# Analog_-_High_Speed_DE.net
KiCad netlist of a schematic drawn in Altium Designer
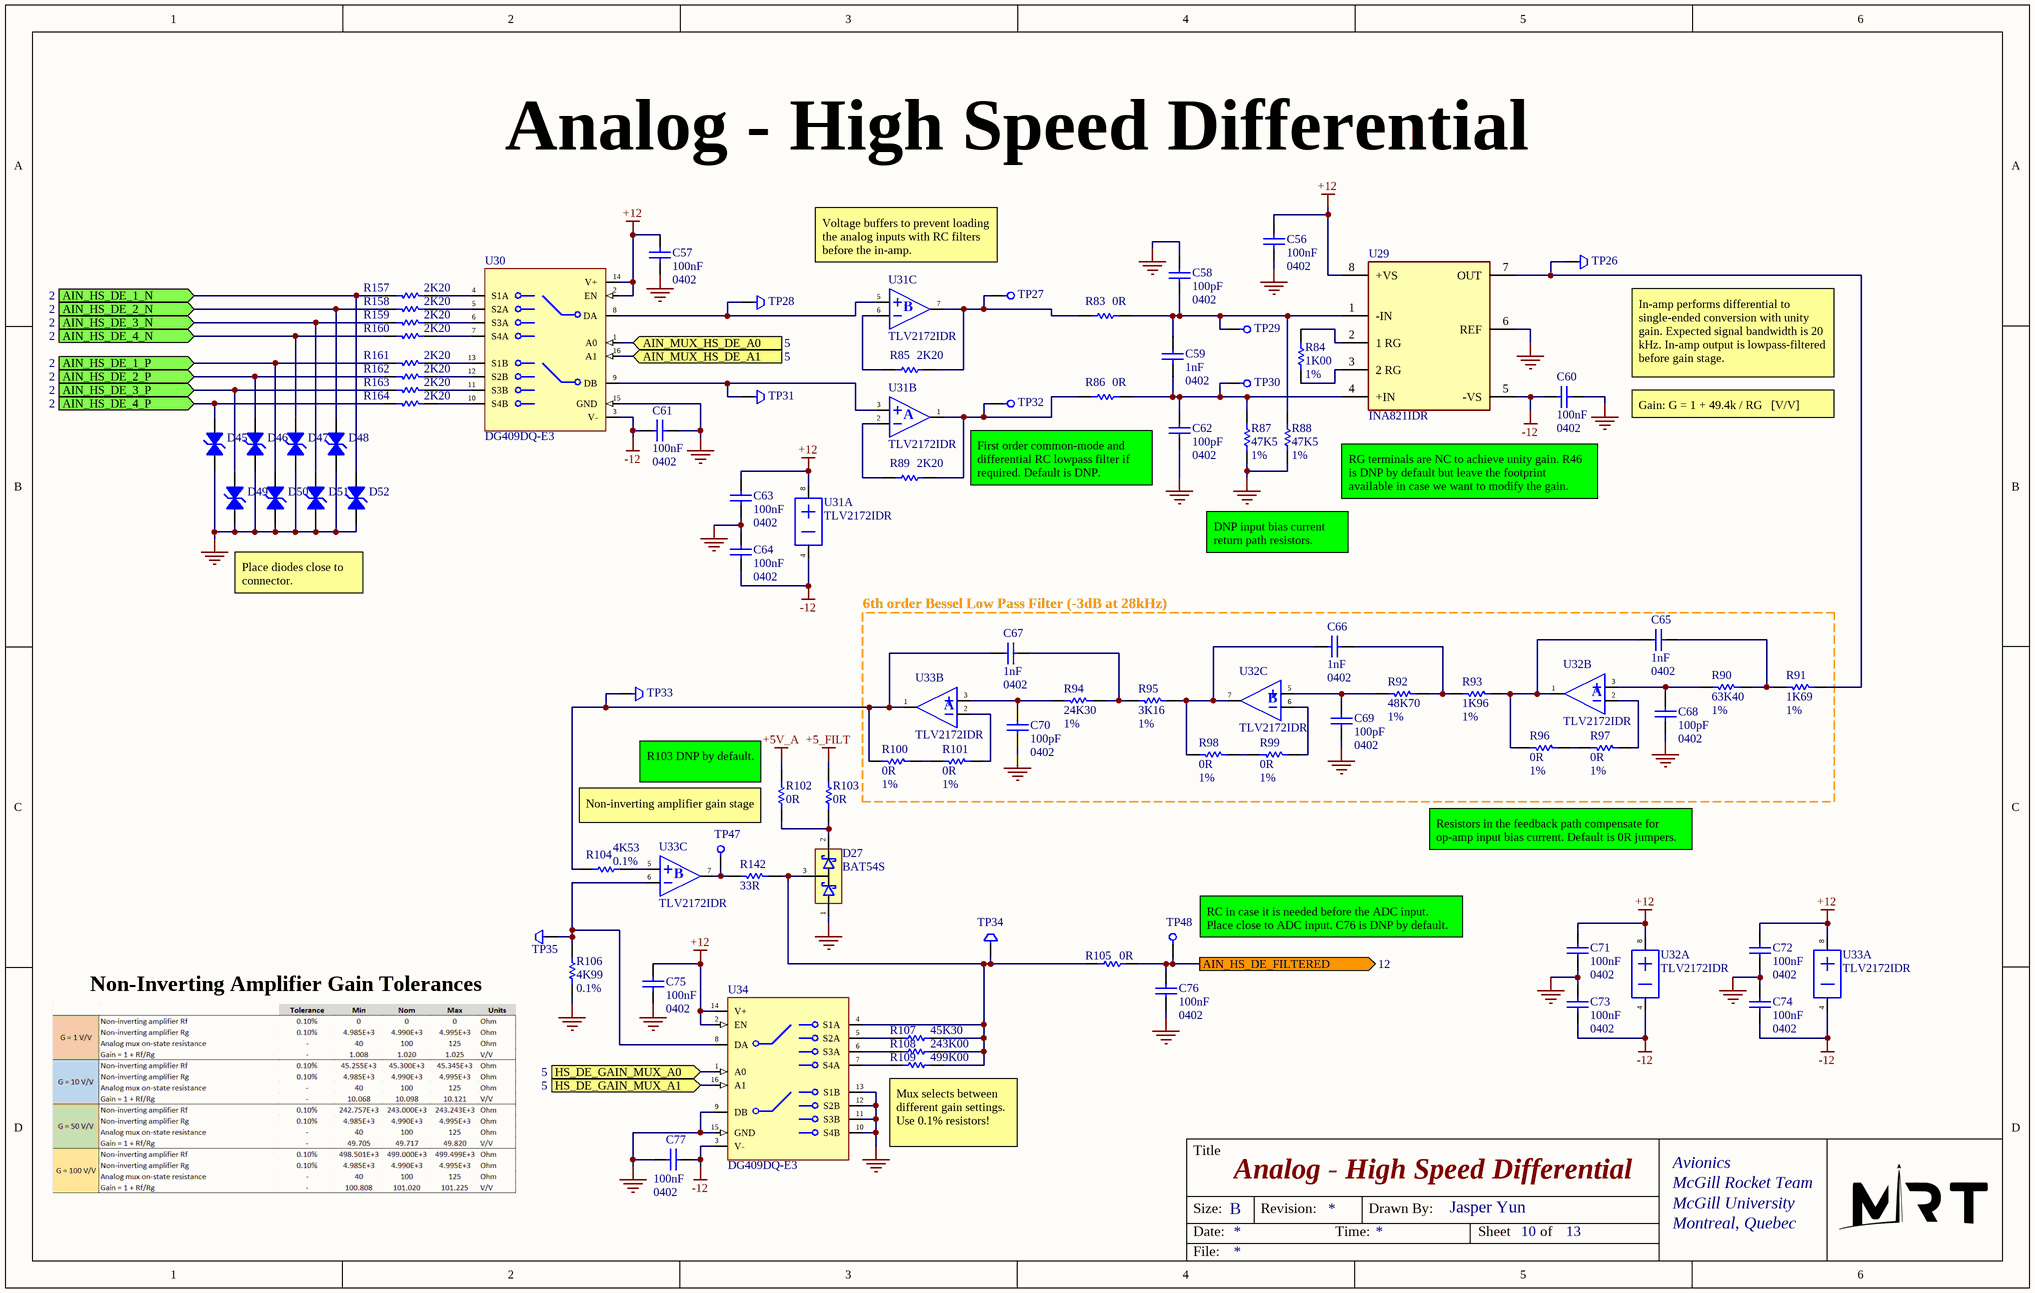
[diagram p0: Analog - High Speed DE.SchDoc]

(export (version "E")
  (design (tool "Eeschema 10.0.6"))
  (components
    (comp (ref "C56")
      (value "100nF")
      (footprint "0402 CAP")
      (description "Capacitor")
      (fields (field (name "ALTIUM_VALUE") "0402") (field (name "PUBLISHER") "Altium Limited"))
      (libsource (lib "Miscellaneous Devices") (part "Cap"))
    )
    (comp (ref "C57")
      (value "100nF")
      (footprint "0402 CAP")
      (description "Capacitor")
      (fields (field (name "ALTIUM_VALUE") "0402") (field (name "PUBLISHER") "Altium Limited"))
      (libsource (lib "Miscellaneous Devices") (part "Cap"))
    )
    (comp (ref "C58")
      (value "100pF")
      (footprint "0402 CAP")
      (description "Capacitor")
      (fields (field (name "ALTIUM_VALUE") "0402") (field (name "PUBLISHER") "Altium Limited"))
      (libsource (lib "Miscellaneous Devices") (part "Cap"))
    )
    (comp (ref "C59")
      (value "1nF")
      (footprint "0402 CAP")
      (description "Capacitor")
      (fields (field (name "ALTIUM_VALUE") "0402") (field (name "PUBLISHER") "Altium Limited"))
      (libsource (lib "Miscellaneous Devices") (part "Cap"))
    )
    (comp (ref "C60")
      (value "100nF")
      (footprint "0402 CAP")
      (description "Capacitor")
      (fields (field (name "ALTIUM_VALUE") "0402") (field (name "PUBLISHER") "Altium Limited"))
      (libsource (lib "Miscellaneous Devices") (part "Cap"))
    )
    (comp (ref "C61")
      (value "100nF")
      (footprint "0402 CAP")
      (description "Capacitor")
      (fields (field (name "ALTIUM_VALUE") "0402") (field (name "PUBLISHER") "Altium Limited"))
      (libsource (lib "Miscellaneous Devices") (part "Cap"))
    )
    (comp (ref "C62")
      (value "100pF")
      (footprint "0402 CAP")
      (description "Capacitor")
      (fields (field (name "ALTIUM_VALUE") "0402") (field (name "PUBLISHER") "Altium Limited"))
      (libsource (lib "Miscellaneous Devices") (part "Cap"))
    )
    (comp (ref "C63")
      (value "100nF")
      (footprint "0402 CAP")
      (description "Capacitor")
      (fields (field (name "ALTIUM_VALUE") "0402") (field (name "PUBLISHER") "Altium Limited"))
      (libsource (lib "Miscellaneous Devices") (part "Cap"))
    )
    (comp (ref "C64")
      (value "100nF")
      (footprint "0402 CAP")
      (description "Capacitor")
      (fields (field (name "ALTIUM_VALUE") "0402") (field (name "PUBLISHER") "Altium Limited"))
      (libsource (lib "Miscellaneous Devices") (part "Cap"))
    )
    (comp (ref "C65")
      (value "1nF")
      (footprint "0402 CAP")
      (description "Capacitor")
      (fields (field (name "ALTIUM_VALUE") "0402") (field (name "PUBLISHER") "Altium Limited"))
      (libsource (lib "Miscellaneous Devices") (part "Cap"))
    )
    (comp (ref "C66")
      (value "1nF")
      (footprint "0402 CAP")
      (description "Capacitor")
      (fields (field (name "ALTIUM_VALUE") "0402") (field (name "PUBLISHER") "Altium Limited"))
      (libsource (lib "Miscellaneous Devices") (part "Cap"))
    )
    (comp (ref "C67")
      (value "1nF")
      (footprint "0402 CAP")
      (description "Capacitor")
      (fields (field (name "ALTIUM_VALUE") "0402") (field (name "PUBLISHER") "Altium Limited"))
      (libsource (lib "Miscellaneous Devices") (part "Cap"))
    )
    (comp (ref "C68")
      (value "100pF")
      (footprint "0402 CAP")
      (description "Capacitor")
      (fields (field (name "ALTIUM_VALUE") "0402") (field (name "PUBLISHER") "Altium Limited"))
      (libsource (lib "Miscellaneous Devices") (part "Cap"))
    )
    (comp (ref "C69")
      (value "100pF")
      (footprint "0402 CAP")
      (description "Capacitor")
      (fields (field (name "ALTIUM_VALUE") "0402") (field (name "PUBLISHER") "Altium Limited"))
      (libsource (lib "Miscellaneous Devices") (part "Cap"))
    )
    (comp (ref "C70")
      (value "100pF")
      (footprint "0402 CAP")
      (description "Capacitor")
      (fields (field (name "ALTIUM_VALUE") "0402") (field (name "PUBLISHER") "Altium Limited"))
      (libsource (lib "Miscellaneous Devices") (part "Cap"))
    )
    (comp (ref "C71")
      (value "100nF")
      (footprint "0402 CAP")
      (description "Capacitor")
      (fields (field (name "ALTIUM_VALUE") "0402") (field (name "PUBLISHER") "Altium Limited"))
      (libsource (lib "Miscellaneous Devices") (part "Cap"))
    )
    (comp (ref "C72")
      (value "100nF")
      (footprint "0402 CAP")
      (description "Capacitor")
      (fields (field (name "ALTIUM_VALUE") "0402") (field (name "PUBLISHER") "Altium Limited"))
      (libsource (lib "Miscellaneous Devices") (part "Cap"))
    )
    (comp (ref "C73")
      (value "100nF")
      (footprint "0402 CAP")
      (description "Capacitor")
      (fields (field (name "ALTIUM_VALUE") "0402") (field (name "PUBLISHER") "Altium Limited"))
      (libsource (lib "Miscellaneous Devices") (part "Cap"))
    )
    (comp (ref "C74")
      (value "100nF")
      (footprint "0402 CAP")
      (description "Capacitor")
      (fields (field (name "ALTIUM_VALUE") "0402") (field (name "PUBLISHER") "Altium Limited"))
      (libsource (lib "Miscellaneous Devices") (part "Cap"))
    )
    (comp (ref "C75")
      (value "100nF")
      (footprint "0402 CAP")
      (description "Capacitor")
      (fields (field (name "ALTIUM_VALUE") "0402") (field (name "PUBLISHER") "Altium Limited"))
      (libsource (lib "Miscellaneous Devices") (part "Cap"))
    )
    (comp (ref "C76")
      (value "100nF")
      (footprint "0402 CAP")
      (description "Capacitor")
      (fields (field (name "ALTIUM_VALUE") "0402") (field (name "PUBLISHER") "Altium Limited"))
      (libsource (lib "Miscellaneous Devices") (part "Cap"))
    )
    (comp (ref "C77")
      (value "100nF")
      (footprint "0402 CAP")
      (description "Capacitor")
      (fields (field (name "ALTIUM_VALUE") "0402") (field (name "PUBLISHER") "Altium Limited"))
      (libsource (lib "Miscellaneous Devices") (part "Cap"))
    )
    (comp (ref "D27")
      (value "BAT54S")
      (footprint "SOT23-3")
      (description "Rectifier Diode Small Signal Schottky 40V 0.3A 5ns 3-Pin SOT-23 T/R")
      (fields
        (field (name "MANUFACTURER") "STMicroelectronics")
        (field (name "MANUFACTURER PART NUMBER") "BAT54SFILM")
      )
      (libsource (lib "MRT SCH Library") (part "Schottky Diode Array BAT54S"))
    )
    (comp (ref "D45")
      (value "D12V0L1B2LP-7B")
      (footprint "DFN1006-2")
      (description "Bidirectional Zener diode")
      (libsource (lib "MRT SCH Library") (part "Diode Zener Bidirectional"))
    )
    (comp (ref "D46")
      (value "D12V0L1B2LP-7B")
      (footprint "DFN1006-2")
      (description "Bidirectional Zener diode")
      (libsource (lib "MRT SCH Library") (part "Diode Zener Bidirectional"))
    )
    (comp (ref "D47")
      (value "D12V0L1B2LP-7B")
      (footprint "DFN1006-2")
      (description "Bidirectional Zener diode")
      (libsource (lib "MRT SCH Library") (part "Diode Zener Bidirectional"))
    )
    (comp (ref "D48")
      (value "D12V0L1B2LP-7B")
      (footprint "DFN1006-2")
      (description "Bidirectional Zener diode")
      (libsource (lib "MRT SCH Library") (part "Diode Zener Bidirectional"))
    )
    (comp (ref "D49")
      (value "D12V0L1B2LP-7B")
      (footprint "DFN1006-2")
      (description "Bidirectional Zener diode")
      (libsource (lib "MRT SCH Library") (part "Diode Zener Bidirectional"))
    )
    (comp (ref "D50")
      (value "D12V0L1B2LP-7B")
      (footprint "DFN1006-2")
      (description "Bidirectional Zener diode")
      (libsource (lib "MRT SCH Library") (part "Diode Zener Bidirectional"))
    )
    (comp (ref "D51")
      (value "D12V0L1B2LP-7B")
      (footprint "DFN1006-2")
      (description "Bidirectional Zener diode")
      (libsource (lib "MRT SCH Library") (part "Diode Zener Bidirectional"))
    )
    (comp (ref "D52")
      (value "D12V0L1B2LP-7B")
      (footprint "DFN1006-2")
      (description "Bidirectional Zener diode")
      (libsource (lib "MRT SCH Library") (part "Diode Zener Bidirectional"))
    )
    (comp (ref "R83")
      (value "0R")
      (footprint "0402 RES")
      (description "Resistor")
      (fields (field (name "PUBLISHER") "Altium Limited"))
      (libsource (lib "Miscellaneous Devices") (part "Res1"))
    )
    (comp (ref "R84")
      (value "1K00")
      (footprint "0402 RES")
      (description "Resistor")
      (fields (field (name "ALTIUM_VALUE") "1%") (field (name "PUBLISHER") "Altium Limited"))
      (libsource (lib "Miscellaneous Devices") (part "Res1"))
    )
    (comp (ref "R85")
      (value "2K20")
      (footprint "0402 RES")
      (description "Resistor")
      (fields (field (name "PUBLISHER") "Altium Limited"))
      (libsource (lib "Miscellaneous Devices") (part "Res1"))
    )
    (comp (ref "R86")
      (value "0R")
      (footprint "0402 RES")
      (description "Resistor")
      (fields (field (name "PUBLISHER") "Altium Limited"))
      (libsource (lib "Miscellaneous Devices") (part "Res1"))
    )
    (comp (ref "R87")
      (value "47K5")
      (footprint "0402 RES")
      (description "Resistor")
      (fields (field (name "ALTIUM_VALUE") "1%") (field (name "PUBLISHER") "Altium Limited"))
      (libsource (lib "Miscellaneous Devices") (part "Res1"))
    )
    (comp (ref "R88")
      (value "47K5")
      (footprint "0402 RES")
      (description "Resistor")
      (fields (field (name "ALTIUM_VALUE") "1%") (field (name "PUBLISHER") "Altium Limited"))
      (libsource (lib "Miscellaneous Devices") (part "Res1"))
    )
    (comp (ref "R89")
      (value "2K20")
      (footprint "0402 RES")
      (description "Resistor")
      (fields (field (name "PUBLISHER") "Altium Limited"))
      (libsource (lib "Miscellaneous Devices") (part "Res1"))
    )
    (comp (ref "R90")
      (value "63K40")
      (footprint "0402 RES")
      (description "Resistor")
      (fields (field (name "ALTIUM_VALUE") "1%") (field (name "PUBLISHER") "Altium Limited"))
      (libsource (lib "Miscellaneous Devices") (part "Res1"))
    )
    (comp (ref "R91")
      (value "1K69")
      (footprint "0402 RES")
      (description "Resistor")
      (fields (field (name "ALTIUM_VALUE") "1%") (field (name "PUBLISHER") "Altium Limited"))
      (libsource (lib "Miscellaneous Devices") (part "Res1"))
    )
    (comp (ref "R92")
      (value "48K70")
      (footprint "0402 RES")
      (description "Resistor")
      (fields (field (name "ALTIUM_VALUE") "1%") (field (name "PUBLISHER") "Altium Limited"))
      (libsource (lib "Miscellaneous Devices") (part "Res1"))
    )
    (comp (ref "R93")
      (value "1K96")
      (footprint "0402 RES")
      (description "Resistor")
      (fields (field (name "ALTIUM_VALUE") "1%") (field (name "PUBLISHER") "Altium Limited"))
      (libsource (lib "Miscellaneous Devices") (part "Res1"))
    )
    (comp (ref "R94")
      (value "24K30")
      (footprint "0402 RES")
      (description "Resistor")
      (fields (field (name "ALTIUM_VALUE") "1%") (field (name "PUBLISHER") "Altium Limited"))
      (libsource (lib "Miscellaneous Devices") (part "Res1"))
    )
    (comp (ref "R95")
      (value "3K16")
      (footprint "0402 RES")
      (description "Resistor")
      (fields (field (name "ALTIUM_VALUE") "1%") (field (name "PUBLISHER") "Altium Limited"))
      (libsource (lib "Miscellaneous Devices") (part "Res1"))
    )
    (comp (ref "R96")
      (value "0R")
      (footprint "0402 RES")
      (description "Resistor")
      (fields (field (name "ALTIUM_VALUE") "1%") (field (name "PUBLISHER") "Altium Limited"))
      (libsource (lib "Miscellaneous Devices") (part "Res1"))
    )
    (comp (ref "R97")
      (value "0R")
      (footprint "0402 RES")
      (description "Resistor")
      (fields (field (name "ALTIUM_VALUE") "1%") (field (name "PUBLISHER") "Altium Limited"))
      (libsource (lib "Miscellaneous Devices") (part "Res1"))
    )
    (comp (ref "R98")
      (value "0R")
      (footprint "0402 RES")
      (description "Resistor")
      (fields (field (name "ALTIUM_VALUE") "1%") (field (name "PUBLISHER") "Altium Limited"))
      (libsource (lib "Miscellaneous Devices") (part "Res1"))
    )
    (comp (ref "R99")
      (value "0R")
      (footprint "0402 RES")
      (description "Resistor")
      (fields (field (name "ALTIUM_VALUE") "1%") (field (name "PUBLISHER") "Altium Limited"))
      (libsource (lib "Miscellaneous Devices") (part "Res1"))
    )
    (comp (ref "R100")
      (value "0R")
      (footprint "0402 RES")
      (description "Resistor")
      (fields (field (name "ALTIUM_VALUE") "1%") (field (name "PUBLISHER") "Altium Limited"))
      (libsource (lib "Miscellaneous Devices") (part "Res1"))
    )
    (comp (ref "R101")
      (value "0R")
      (footprint "0402 RES")
      (description "Resistor")
      (fields (field (name "ALTIUM_VALUE") "1%") (field (name "PUBLISHER") "Altium Limited"))
      (libsource (lib "Miscellaneous Devices") (part "Res1"))
    )
    (comp (ref "R102")
      (value "0R")
      (footprint "0402 RES")
      (description "Resistor")
      (fields (field (name "PUBLISHER") "Altium Limited"))
      (libsource (lib "Miscellaneous Devices") (part "Res1"))
    )
    (comp (ref "R103")
      (value "0R")
      (footprint "0402 RES")
      (description "Resistor")
      (fields (field (name "PUBLISHER") "Altium Limited"))
      (libsource (lib "Miscellaneous Devices") (part "Res1"))
    )
    (comp (ref "R104")
      (value "4K53")
      (footprint "0402 RES")
      (description "Resistor")
      (fields (field (name "ALTIUM_VALUE") "0.1%") (field (name "PUBLISHER") "Altium Limited"))
      (libsource (lib "Miscellaneous Devices") (part "Res1"))
    )
    (comp (ref "R105")
      (value "0R")
      (footprint "0402 RES")
      (description "Resistor")
      (fields (field (name "PUBLISHER") "Altium Limited"))
      (libsource (lib "Miscellaneous Devices") (part "Res1"))
    )
    (comp (ref "R106")
      (value "4K99")
      (footprint "0402 RES")
      (description "Resistor")
      (fields (field (name "ALTIUM_VALUE") "0.1%") (field (name "PUBLISHER") "Altium Limited"))
      (libsource (lib "Miscellaneous Devices") (part "Res1"))
    )
    (comp (ref "R107")
      (value "45K30")
      (footprint "0402 RES")
      (description "Resistor")
      (fields (field (name "PUBLISHER") "Altium Limited"))
      (libsource (lib "Miscellaneous Devices") (part "Res1"))
    )
    (comp (ref "R108")
      (value "243K00")
      (footprint "0402 RES")
      (description "Resistor")
      (fields (field (name "PUBLISHER") "Altium Limited"))
      (libsource (lib "Miscellaneous Devices") (part "Res1"))
    )
    (comp (ref "R109")
      (value "499K00")
      (footprint "0402 RES")
      (description "Resistor")
      (fields (field (name "PUBLISHER") "Altium Limited"))
      (libsource (lib "Miscellaneous Devices") (part "Res1"))
    )
    (comp (ref "R142")
      (value "33R")
      (footprint "0402 RES")
      (description "Resistor")
      (fields (field (name "PUBLISHER") "Altium Limited"))
      (libsource (lib "Miscellaneous Devices") (part "Res1"))
    )
    (comp (ref "R157")
      (value "2K20")
      (footprint "0402 RES")
      (description "Resistor")
      (fields (field (name "PUBLISHER") "Altium Limited"))
      (libsource (lib "Miscellaneous Devices") (part "Res1"))
    )
    (comp (ref "R158")
      (value "2K20")
      (footprint "0402 RES")
      (description "Resistor")
      (fields (field (name "PUBLISHER") "Altium Limited"))
      (libsource (lib "Miscellaneous Devices") (part "Res1"))
    )
    (comp (ref "R159")
      (value "2K20")
      (footprint "0402 RES")
      (description "Resistor")
      (fields (field (name "PUBLISHER") "Altium Limited"))
      (libsource (lib "Miscellaneous Devices") (part "Res1"))
    )
    (comp (ref "R160")
      (value "2K20")
      (footprint "0402 RES")
      (description "Resistor")
      (fields (field (name "PUBLISHER") "Altium Limited"))
      (libsource (lib "Miscellaneous Devices") (part "Res1"))
    )
    (comp (ref "R161")
      (value "2K20")
      (footprint "0402 RES")
      (description "Resistor")
      (fields (field (name "PUBLISHER") "Altium Limited"))
      (libsource (lib "Miscellaneous Devices") (part "Res1"))
    )
    (comp (ref "R162")
      (value "2K20")
      (footprint "0402 RES")
      (description "Resistor")
      (fields (field (name "PUBLISHER") "Altium Limited"))
      (libsource (lib "Miscellaneous Devices") (part "Res1"))
    )
    (comp (ref "R163")
      (value "2K20")
      (footprint "0402 RES")
      (description "Resistor")
      (fields (field (name "PUBLISHER") "Altium Limited"))
      (libsource (lib "Miscellaneous Devices") (part "Res1"))
    )
    (comp (ref "R164")
      (value "2K20")
      (footprint "0402 RES")
      (description "Resistor")
      (fields (field (name "PUBLISHER") "Altium Limited"))
      (libsource (lib "Miscellaneous Devices") (part "Res1"))
    )
    (comp (ref "TP26")
      (value "Test Point - Keystone 5015")
      (footprint "Test Point Keystone 5015")
      (description "Keystone 5015 Test point")
      (libsource (lib "MRT SCH Library") (part "Test Point - Keystone 5015"))
    )
    (comp (ref "TP27")
      (value "Test Point - SMD Pad")
      (footprint "TEST POINT SMD PAD")
      (description "SMD Pad test point")
      (libsource (lib "MRT SCH Library") (part "Test Point - SMD Pad"))
    )
    (comp (ref "TP28")
      (value "Test Point - Keystone 5015")
      (footprint "Test Point Keystone 5015")
      (description "Keystone 5015 Test point")
      (libsource (lib "MRT SCH Library") (part "Test Point - Keystone 5015"))
    )
    (comp (ref "TP29")
      (value "Test Point - SMD Pad")
      (footprint "TEST POINT SMD PAD")
      (description "SMD Pad test point")
      (libsource (lib "MRT SCH Library") (part "Test Point - SMD Pad"))
    )
    (comp (ref "TP30")
      (value "Test Point - SMD Pad")
      (footprint "TEST POINT SMD PAD")
      (description "SMD Pad test point")
      (libsource (lib "MRT SCH Library") (part "Test Point - SMD Pad"))
    )
    (comp (ref "TP31")
      (value "Test Point - Keystone 5015")
      (footprint "Test Point Keystone 5015")
      (description "Keystone 5015 Test point")
      (libsource (lib "MRT SCH Library") (part "Test Point - Keystone 5015"))
    )
    (comp (ref "TP32")
      (value "Test Point - SMD Pad")
      (footprint "TEST POINT SMD PAD")
      (description "SMD Pad test point")
      (libsource (lib "MRT SCH Library") (part "Test Point - SMD Pad"))
    )
    (comp (ref "TP33")
      (value "Test Point - Keystone 5015")
      (footprint "Test Point Keystone 5015")
      (description "Keystone 5015 Test point")
      (libsource (lib "MRT SCH Library") (part "Test Point - Keystone 5015"))
    )
    (comp (ref "TP34")
      (value "Test Point - Keystone 5015")
      (footprint "Test Point Keystone 5015")
      (description "Keystone 5015 Test point")
      (libsource (lib "MRT SCH Library") (part "Test Point - Keystone 5015"))
    )
    (comp (ref "TP35")
      (value "Test Point - Keystone 5015")
      (footprint "Test Point Keystone 5015")
      (description "Keystone 5015 Test point")
      (libsource (lib "MRT SCH Library") (part "Test Point - Keystone 5015"))
    )
    (comp (ref "TP47")
      (value "Test Point - SMD Pad")
      (footprint "TEST POINT SMD PAD")
      (description "SMD Pad test point")
      (libsource (lib "MRT SCH Library") (part "Test Point - SMD Pad"))
    )
    (comp (ref "TP48")
      (value "Test Point - SMD Pad")
      (footprint "TEST POINT SMD PAD")
      (description "SMD Pad test point")
      (libsource (lib "MRT SCH Library") (part "Test Point - SMD Pad"))
    )
    (comp (ref "U29")
      (value "INA821IDR")
      (footprint "FP-D0008A-IPC_A")
      (description "IC INST AMP 1 CIRCUIT 8SOIC")
      (libsource (lib "Altium Content Vault") (part "f8dea4e880bbf27f1efc339ce0e0823"))
    )
    (comp (ref "U30")
      (value "DG409DQ-E3")
      (footprint "TSSOP-16")
      (description "DG409 Series 20 V 8-Ch/Dual 4-Ch High-Performance CMOS Analog Multiplexer")
      (fields (field (name "MANUFACTURER") "Vishay Siliconix"))
      (libsource (lib "MRT SCH Library") (part "Analog Mux DG409DQ-E3"))
    )
    (comp (ref "U31")
      (value "TLV2172IDR")
      (footprint "SOIC-8")
      (fields
        (field (name "MANUFACTURER") "Texas Instruments")
        (field (name "MANUFACTURER PART NUMBER") "RC4580IDR")
      )
      (libsource (lib "MRT SCH Library") (part "OP AMP RC4580"))
    )
    (comp (ref "U32")
      (value "TLV2172IDR")
      (footprint "SOIC-8")
      (fields
        (field (name "MANUFACTURER") "Texas Instruments")
        (field (name "MANUFACTURER PART NUMBER") "RC4580IDR")
      )
      (libsource (lib "MRT SCH Library") (part "OP AMP RC4580"))
    )
    (comp (ref "U33")
      (value "TLV2172IDR")
      (footprint "SOIC-8")
      (fields
        (field (name "MANUFACTURER") "Texas Instruments")
        (field (name "MANUFACTURER PART NUMBER") "RC4580IDR")
      )
      (libsource (lib "MRT SCH Library") (part "OP AMP RC4580"))
    )
    (comp (ref "U34")
      (value "DG409DQ-E3")
      (footprint "TSSOP-16")
      (description "DG409 Series 20 V 8-Ch/Dual 4-Ch High-Performance CMOS Analog Multiplexer")
      (fields (field (name "MANUFACTURER") "Vishay Siliconix"))
      (libsource (lib "") (part "Analog Mux DG409DQ-E3_1"))
    )
  )
  (nets
    (net (code "1") (name "+5V_A") (class "Default")
      (node (ref "R102") (pin "1") (pinfunction "1_1") (pintype "passive"))
    )
    (net (code "2") (name "+5_FILT") (class "Default")
      (node (ref "R103") (pin "1") (pinfunction "1_1") (pintype "passive"))
    )
    (net (code "3") (name "+12") (class "Default")
      (node (ref "C56") (pin "2") (pinfunction "2_2") (pintype "passive"))
      (node (ref "C57") (pin "2") (pinfunction "2_2") (pintype "passive"))
      (node (ref "C63") (pin "2") (pinfunction "2_2") (pintype "passive"))
      (node (ref "C71") (pin "2") (pinfunction "2_2") (pintype "passive"))
      (node (ref "C72") (pin "2") (pinfunction "2_2") (pintype "passive"))
      (node (ref "C75") (pin "2") (pinfunction "2_2") (pintype "passive"))
      (node (ref "U29") (pin "8") (pinfunction "+VS_8") (pintype "power_in"))
      (node (ref "U30") (pin "14") (pinfunction "V+_14") (pintype "passive"))
      (node (ref "U30") (pin "2") (pinfunction "EN_2") (pintype "input"))
      (node (ref "U31") (pin "8") (pinfunction "VCC+_8") (pintype "passive"))
      (node (ref "U32") (pin "8") (pinfunction "VCC+_8") (pintype "passive"))
      (node (ref "U33") (pin "8") (pinfunction "VCC+_8") (pintype "passive"))
      (node (ref "U34") (pin "14") (pinfunction "V+_14") (pintype "passive"))
      (node (ref "U34") (pin "2") (pinfunction "EN_2") (pintype "input"))
    )
    (net (code "4") (name "-12") (class "Default")
      (node (ref "C60") (pin "2") (pinfunction "2_2") (pintype "passive"))
      (node (ref "C61") (pin "2") (pinfunction "2_2") (pintype "passive"))
      (node (ref "C64") (pin "1") (pinfunction "1_1") (pintype "passive"))
      (node (ref "C73") (pin "1") (pinfunction "1_1") (pintype "passive"))
      (node (ref "C74") (pin "1") (pinfunction "1_1") (pintype "passive"))
      (node (ref "C77") (pin "2") (pinfunction "2_2") (pintype "passive"))
      (node (ref "U29") (pin "5") (pinfunction "-VS_5") (pintype "power_in"))
      (node (ref "U30") (pin "3") (pinfunction "V-_3") (pintype "passive"))
      (node (ref "U31") (pin "4") (pinfunction "VCC-_4") (pintype "passive"))
      (node (ref "U32") (pin "4") (pinfunction "VCC-_4") (pintype "passive"))
      (node (ref "U33") (pin "4") (pinfunction "VCC-_4") (pintype "passive"))
      (node (ref "U34") (pin "3") (pinfunction "V-_3") (pintype "passive"))
    )
    (net (code "5") (name "/AIN_HS_DE_1_N") (class "Default")
      (node (ref "D52") (pin "2") (pinfunction "2_2") (pintype "passive"))
      (node (ref "R157") (pin "1") (pinfunction "1_1") (pintype "passive"))
    )
    (net (code "6") (name "/AIN_HS_DE_1_P") (class "Default")
      (node (ref "D50") (pin "2") (pinfunction "2_2") (pintype "passive"))
      (node (ref "R161") (pin "1") (pinfunction "1_1") (pintype "passive"))
    )
    (net (code "7") (name "/AIN_HS_DE_2_N") (class "Default")
      (node (ref "D48") (pin "2") (pinfunction "2_2") (pintype "passive"))
      (node (ref "R158") (pin "1") (pinfunction "1_1") (pintype "passive"))
    )
    (net (code "8") (name "/AIN_HS_DE_2_P") (class "Default")
      (node (ref "D46") (pin "2") (pinfunction "2_2") (pintype "passive"))
      (node (ref "R162") (pin "1") (pinfunction "1_1") (pintype "passive"))
    )
    (net (code "9") (name "/AIN_HS_DE_3_N") (class "Default")
      (node (ref "D51") (pin "2") (pinfunction "2_2") (pintype "passive"))
      (node (ref "R159") (pin "1") (pinfunction "1_1") (pintype "passive"))
    )
    (net (code "10") (name "/AIN_HS_DE_3_P") (class "Default")
      (node (ref "D49") (pin "2") (pinfunction "2_2") (pintype "passive"))
      (node (ref "R163") (pin "1") (pinfunction "1_1") (pintype "passive"))
    )
    (net (code "11") (name "/AIN_HS_DE_4_N") (class "Default")
      (node (ref "D47") (pin "2") (pinfunction "2_2") (pintype "passive"))
      (node (ref "R160") (pin "1") (pinfunction "1_1") (pintype "passive"))
    )
    (net (code "12") (name "/AIN_HS_DE_4_P") (class "Default")
      (node (ref "D45") (pin "2") (pinfunction "2_2") (pintype "passive"))
      (node (ref "R164") (pin "1") (pinfunction "1_1") (pintype "passive"))
    )
    (net (code "13") (name "/AIN_HS_DE_FILTERED") (class "Default")
      (node (ref "C76") (pin "2") (pinfunction "2_2") (pintype "passive"))
      (node (ref "R105") (pin "1") (pinfunction "1_1") (pintype "passive"))
      (node (ref "TP48") (pin "1") (pinfunction "1_1") (pintype "passive"))
    )
    (net (code "14") (name "/AIN_MUX_HS_DE_A0") (class "Default")
      (node (ref "U30") (pin "1") (pinfunction "A0_1") (pintype "input"))
    )
    (net (code "15") (name "/AIN_MUX_HS_DE_A1") (class "Default")
      (node (ref "U30") (pin "16") (pinfunction "A1_16") (pintype "input"))
    )
    (net (code "16") (name "/HS_DE_GAIN_MUX_A0") (class "Default")
      (node (ref "U34") (pin "1") (pinfunction "A0_1") (pintype "input"))
    )
    (net (code "17") (name "/HS_DE_GAIN_MUX_A1") (class "Default")
      (node (ref "U34") (pin "16") (pinfunction "A1_16") (pintype "input"))
    )
    (net (code "18") (name "GND") (class "Default")
      (node (ref "C56") (pin "1") (pinfunction "1_1") (pintype "passive"))
      (node (ref "C57") (pin "1") (pinfunction "1_1") (pintype "passive"))
      (node (ref "C58") (pin "2") (pinfunction "2_2") (pintype "passive"))
      (node (ref "C60") (pin "1") (pinfunction "1_1") (pintype "passive"))
      (node (ref "C61") (pin "1") (pinfunction "1_1") (pintype "passive"))
      (node (ref "C62") (pin "1") (pinfunction "1_1") (pintype "passive"))
      (node (ref "C63") (pin "1") (pinfunction "1_1") (pintype "passive"))
      (node (ref "C64") (pin "2") (pinfunction "2_2") (pintype "passive"))
      (node (ref "C68") (pin "1") (pinfunction "1_1") (pintype "passive"))
      (node (ref "C69") (pin "1") (pinfunction "1_1") (pintype "passive"))
      (node (ref "C70") (pin "1") (pinfunction "1_1") (pintype "passive"))
      (node (ref "C71") (pin "1") (pinfunction "1_1") (pintype "passive"))
      (node (ref "C72") (pin "1") (pinfunction "1_1") (pintype "passive"))
      (node (ref "C73") (pin "2") (pinfunction "2_2") (pintype "passive"))
      (node (ref "C74") (pin "2") (pinfunction "2_2") (pintype "passive"))
      (node (ref "C75") (pin "1") (pinfunction "1_1") (pintype "passive"))
      (node (ref "C76") (pin "1") (pinfunction "1_1") (pintype "passive"))
      (node (ref "C77") (pin "1") (pinfunction "1_1") (pintype "passive"))
      (node (ref "D27") (pin "1") (pinfunction "1_1") (pintype "passive"))
      (node (ref "D45") (pin "1") (pinfunction "1_1") (pintype "passive"))
      (node (ref "D46") (pin "1") (pinfunction "1_1") (pintype "passive"))
      (node (ref "D47") (pin "1") (pinfunction "1_1") (pintype "passive"))
      (node (ref "D48") (pin "1") (pinfunction "1_1") (pintype "passive"))
      (node (ref "D49") (pin "1") (pinfunction "1_1") (pintype "passive"))
      (node (ref "D50") (pin "1") (pinfunction "1_1") (pintype "passive"))
      (node (ref "D51") (pin "1") (pinfunction "1_1") (pintype "passive"))
      (node (ref "D52") (pin "1") (pinfunction "1_1") (pintype "passive"))
      (node (ref "R106") (pin "1") (pinfunction "1_1") (pintype "passive"))
      (node (ref "R87") (pin "1") (pinfunction "1_1") (pintype "passive"))
      (node (ref "R88") (pin "1") (pinfunction "1_1") (pintype "passive"))
      (node (ref "U29") (pin "6") (pinfunction "REF_6") (pintype "passive"))
      (node (ref "U30") (pin "15") (pinfunction "GND_15") (pintype "input"))
      (node (ref "U34") (pin "10") (pinfunction "S4B_10") (pintype "passive"))
      (node (ref "U34") (pin "11") (pinfunction "S3B_11") (pintype "passive"))
      (node (ref "U34") (pin "12") (pinfunction "S2B_12") (pintype "passive"))
      (node (ref "U34") (pin "13") (pinfunction "S1B_13") (pintype "passive"))
      (node (ref "U34") (pin "15") (pinfunction "GND_15") (pintype "input"))
      (node (ref "U34") (pin "9") (pinfunction "DB_9") (pintype "passive"))
    )
    (net (code "19") (name "Net-(C65-Pad1)") (class "Default")
      (node (ref "C65") (pin "1") (pinfunction "1_1") (pintype "passive"))
      (node (ref "R93") (pin "1") (pinfunction "1_1") (pintype "passive"))
      (node (ref "R96") (pin "2") (pinfunction "2_2") (pintype "passive"))
      (node (ref "U32") (pin "1") (pinfunction "1_1") (pintype "passive"))
    )
    (net (code "20") (name "Net-(C65-Pad2)") (class "Default")
      (node (ref "C65") (pin "2") (pinfunction "2_2") (pintype "passive"))
      (node (ref "R90") (pin "1") (pinfunction "1_1") (pintype "passive"))
      (node (ref "R91") (pin "2") (pinfunction "2_2") (pintype "passive"))
    )
    (net (code "21") (name "Net-(C66-Pad1)") (class "Default")
      (node (ref "C66") (pin "1") (pinfunction "1_1") (pintype "passive"))
      (node (ref "R95") (pin "1") (pinfunction "1_1") (pintype "passive"))
      (node (ref "R98") (pin "2") (pinfunction "2_2") (pintype "passive"))
      (node (ref "U32") (pin "7") (pinfunction "7_7") (pintype "passive"))
    )
    (net (code "22") (name "Net-(C66-Pad2)") (class "Default")
      (node (ref "C66") (pin "2") (pinfunction "2_2") (pintype "passive"))
      (node (ref "R92") (pin "1") (pinfunction "1_1") (pintype "passive"))
      (node (ref "R93") (pin "2") (pinfunction "2_2") (pintype "passive"))
    )
    (net (code "23") (name "Net-(C67-Pad1)") (class "Default")
      (node (ref "C67") (pin "1") (pinfunction "1_1") (pintype "passive"))
      (node (ref "R100") (pin "2") (pinfunction "2_2") (pintype "passive"))
      (node (ref "R104") (pin "2") (pinfunction "2_2") (pintype "passive"))
      (node (ref "TP33") (pin "1") (pinfunction "1_1") (pintype "passive"))
      (node (ref "U33") (pin "1") (pinfunction "1_1") (pintype "passive"))
    )
    (net (code "24") (name "Net-(C67-Pad2)") (class "Default")
      (node (ref "C67") (pin "2") (pinfunction "2_2") (pintype "passive"))
      (node (ref "R94") (pin "1") (pinfunction "1_1") (pintype "passive"))
      (node (ref "R95") (pin "2") (pinfunction "2_2") (pintype "passive"))
    )
    (net (code "25") (name "Net-(C68-Pad2)") (class "Default")
      (node (ref "C68") (pin "2") (pinfunction "2_2") (pintype "passive"))
      (node (ref "R90") (pin "2") (pinfunction "2_2") (pintype "passive"))
      (node (ref "U32") (pin "3") (pinfunction "3_3") (pintype "passive"))
    )
    (net (code "26") (name "Net-(C69-Pad2)") (class "Default")
      (node (ref "C69") (pin "2") (pinfunction "2_2") (pintype "passive"))
      (node (ref "R92") (pin "2") (pinfunction "2_2") (pintype "passive"))
      (node (ref "U32") (pin "5") (pinfunction "5_5") (pintype "passive"))
    )
    (net (code "27") (name "Net-(C70-Pad2)") (class "Default")
      (node (ref "C70") (pin "2") (pinfunction "2_2") (pintype "passive"))
      (node (ref "R94") (pin "2") (pinfunction "2_2") (pintype "passive"))
      (node (ref "U33") (pin "3") (pinfunction "3_3") (pintype "passive"))
    )
    (net (code "28") (name "Net-(D27-Pad2)") (class "Default")
      (node (ref "D27") (pin "2") (pinfunction "2_2") (pintype "passive"))
      (node (ref "R102") (pin "2") (pinfunction "2_2") (pintype "passive"))
      (node (ref "R103") (pin "2") (pinfunction "2_2") (pintype "passive"))
    )
    (net (code "29") (name "Net-(R83-Pad2)") (class "Default")
      (node (ref "R83") (pin "2") (pinfunction "2_2") (pintype "passive"))
      (node (ref "R85") (pin "1") (pinfunction "1_1") (pintype "passive"))
      (node (ref "TP27") (pin "1") (pinfunction "1_1") (pintype "passive"))
      (node (ref "U31") (pin "7") (pinfunction "7_7") (pintype "passive"))
    )
    (net (code "30") (name "Net-(R85-Pad2)") (class "Default")
      (node (ref "R85") (pin "2") (pinfunction "2_2") (pintype "passive"))
      (node (ref "U31") (pin "6") (pinfunction "6_6") (pintype "passive"))
    )
    (net (code "31") (name "Net-(R86-Pad2)") (class "Default")
      (node (ref "R86") (pin "2") (pinfunction "2_2") (pintype "passive"))
      (node (ref "R89") (pin "1") (pinfunction "1_1") (pintype "passive"))
      (node (ref "TP32") (pin "1") (pinfunction "1_1") (pintype "passive"))
      (node (ref "U31") (pin "1") (pinfunction "1_1") (pintype "passive"))
    )
    (net (code "32") (name "Net-(R89-Pad2)") (class "Default")
      (node (ref "R89") (pin "2") (pinfunction "2_2") (pintype "passive"))
      (node (ref "U31") (pin "2") (pinfunction "2_2") (pintype "passive"))
    )
    (net (code "33") (name "Net-(R96-Pad1)") (class "Default")
      (node (ref "R96") (pin "1") (pinfunction "1_1") (pintype "passive"))
      (node (ref "R97") (pin "2") (pinfunction "2_2") (pintype "passive"))
    )
    (net (code "34") (name "Net-(R97-Pad1)") (class "Default")
      (node (ref "R97") (pin "1") (pinfunction "1_1") (pintype "passive"))
      (node (ref "U32") (pin "2") (pinfunction "2_2") (pintype "passive"))
    )
    (net (code "35") (name "Net-(R98-Pad1)") (class "Default")
      (node (ref "R98") (pin "1") (pinfunction "1_1") (pintype "passive"))
      (node (ref "R99") (pin "2") (pinfunction "2_2") (pintype "passive"))
    )
    (net (code "36") (name "Net-(R99-Pad1)") (class "Default")
      (node (ref "R99") (pin "1") (pinfunction "1_1") (pintype "passive"))
      (node (ref "U32") (pin "6") (pinfunction "6_6") (pintype "passive"))
    )
    (net (code "37") (name "Net-(R100-Pad1)") (class "Default")
      (node (ref "R100") (pin "1") (pinfunction "1_1") (pintype "passive"))
      (node (ref "R101") (pin "2") (pinfunction "2_2") (pintype "passive"))
    )
    (net (code "38") (name "Net-(R101-Pad1)") (class "Default")
      (node (ref "R101") (pin "1") (pinfunction "1_1") (pintype "passive"))
      (node (ref "U33") (pin "2") (pinfunction "2_2") (pintype "passive"))
    )
    (net (code "39") (name "Net-(R104-Pad1)") (class "Default")
      (node (ref "R104") (pin "1") (pinfunction "1_1") (pintype "passive"))
      (node (ref "U33") (pin "5") (pinfunction "5_5") (pintype "passive"))
    )
    (net (code "40") (name "Net-(R142-Pad1)") (class "Default")
      (node (ref "R142") (pin "1") (pinfunction "1_1") (pintype "passive"))
      (node (ref "TP47") (pin "1") (pinfunction "1_1") (pintype "passive"))
      (node (ref "U33") (pin "7") (pinfunction "7_7") (pintype "passive"))
    )
    (net (code "41") (name "Net-(U29-+IN)") (class "Default")
      (node (ref "C59") (pin "1") (pinfunction "1_1") (pintype "passive"))
      (node (ref "C62") (pin "2") (pinfunction "2_2") (pintype "passive"))
      (node (ref "R86") (pin "1") (pinfunction "1_1") (pintype "passive"))
      (node (ref "R87") (pin "2") (pinfunction "2_2") (pintype "passive"))
      (node (ref "TP30") (pin "1") (pinfunction "1_1") (pintype "passive"))
      (node (ref "U29") (pin "4") (pinfunction "+IN_4") (pintype "tri_state"))
    )
    (net (code "42") (name "Net-(U29--IN)") (class "Default")
      (node (ref "C58") (pin "1") (pinfunction "1_1") (pintype "passive"))
      (node (ref "C59") (pin "2") (pinfunction "2_2") (pintype "passive"))
      (node (ref "R83") (pin "1") (pinfunction "1_1") (pintype "passive"))
      (node (ref "R88") (pin "2") (pinfunction "2_2") (pintype "passive"))
      (node (ref "TP29") (pin "1") (pinfunction "1_1") (pintype "passive"))
      (node (ref "U29") (pin "1") (pinfunction "-IN_1") (pintype "tri_state"))
    )
    (net (code "43") (name "Net-(U29-1_RG)") (class "Default")
      (node (ref "R84") (pin "2") (pinfunction "2_2") (pintype "passive"))
      (node (ref "U29") (pin "2") (pinfunction "1_RG_2") (pintype "passive"))
    )
    (net (code "44") (name "Net-(U29-2_RG)") (class "Default")
      (node (ref "R84") (pin "1") (pinfunction "1_1") (pintype "passive"))
      (node (ref "U29") (pin "3") (pinfunction "2_RG_3") (pintype "passive"))
    )
    (net (code "45") (name "Net-(U29-OUT)") (class "Default")
      (node (ref "R91") (pin "1") (pinfunction "1_1") (pintype "passive"))
      (node (ref "TP26") (pin "1") (pinfunction "1_1") (pintype "passive"))
      (node (ref "U29") (pin "7") (pinfunction "OUT_7") (pintype "passive"))
    )
    (net (code "46") (name "Net-(U30-DA)") (class "Default")
      (node (ref "TP28") (pin "1") (pinfunction "1_1") (pintype "passive"))
      (node (ref "U30") (pin "8") (pinfunction "DA_8") (pintype "passive"))
      (node (ref "U31") (pin "5") (pinfunction "5_5") (pintype "passive"))
    )
    (net (code "47") (name "Net-(U30-DB)") (class "Default")
      (node (ref "TP31") (pin "1") (pinfunction "1_1") (pintype "passive"))
      (node (ref "U30") (pin "9") (pinfunction "DB_9") (pintype "passive"))
      (node (ref "U31") (pin "3") (pinfunction "3_3") (pintype "passive"))
    )
    (net (code "48") (name "Net-(U30-S1A)") (class "Default")
      (node (ref "R157") (pin "2") (pinfunction "2_2") (pintype "passive"))
      (node (ref "U30") (pin "4") (pinfunction "S1A_4") (pintype "passive"))
    )
    (net (code "49") (name "Net-(U30-S1B)") (class "Default")
      (node (ref "R161") (pin "2") (pinfunction "2_2") (pintype "passive"))
      (node (ref "U30") (pin "13") (pinfunction "S1B_13") (pintype "passive"))
    )
    (net (code "50") (name "Net-(U30-S2A)") (class "Default")
      (node (ref "R158") (pin "2") (pinfunction "2_2") (pintype "passive"))
      (node (ref "U30") (pin "5") (pinfunction "S2A_5") (pintype "passive"))
    )
    (net (code "51") (name "Net-(U30-S2B)") (class "Default")
      (node (ref "R162") (pin "2") (pinfunction "2_2") (pintype "passive"))
      (node (ref "U30") (pin "12") (pinfunction "S2B_12") (pintype "passive"))
    )
    (net (code "52") (name "Net-(U30-S3A)") (class "Default")
      (node (ref "R159") (pin "2") (pinfunction "2_2") (pintype "passive"))
      (node (ref "U30") (pin "6") (pinfunction "S3A_6") (pintype "passive"))
    )
    (net (code "53") (name "Net-(U30-S3B)") (class "Default")
      (node (ref "R163") (pin "2") (pinfunction "2_2") (pintype "passive"))
      (node (ref "U30") (pin "11") (pinfunction "S3B_11") (pintype "passive"))
    )
    (net (code "54") (name "Net-(U30-S4A)") (class "Default")
      (node (ref "R160") (pin "2") (pinfunction "2_2") (pintype "passive"))
      (node (ref "U30") (pin "7") (pinfunction "S4A_7") (pintype "passive"))
    )
    (net (code "55") (name "Net-(U30-S4B)") (class "Default")
      (node (ref "R164") (pin "2") (pinfunction "2_2") (pintype "passive"))
      (node (ref "U30") (pin "10") (pinfunction "S4B_10") (pintype "passive"))
    )
    (net (code "56") (name "Net-(U34-DA)") (class "Default")
      (node (ref "R106") (pin "2") (pinfunction "2_2") (pintype "passive"))
      (node (ref "TP35") (pin "1") (pinfunction "1_1") (pintype "passive"))
      (node (ref "U33") (pin "6") (pinfunction "6_6") (pintype "passive"))
      (node (ref "U34") (pin "8") (pinfunction "DA_8") (pintype "passive"))
    )
    (net (code "57") (name "Net-(U34-S1A)") (class "Default")
      (node (ref "D27") (pin "3") (pinfunction "3_3") (pintype "passive"))
      (node (ref "R105") (pin "2") (pinfunction "2_2") (pintype "passive"))
      (node (ref "R107") (pin "1") (pinfunction "1_1") (pintype "passive"))
      (node (ref "R108") (pin "1") (pinfunction "1_1") (pintype "passive"))
      (node (ref "R109") (pin "1") (pinfunction "1_1") (pintype "passive"))
      (node (ref "R142") (pin "2") (pinfunction "2_2") (pintype "passive"))
      (node (ref "TP34") (pin "1") (pinfunction "1_1") (pintype "passive"))
      (node (ref "U34") (pin "4") (pinfunction "S1A_4") (pintype "passive"))
    )
    (net (code "58") (name "Net-(U34-S2A)") (class "Default")
      (node (ref "R107") (pin "2") (pinfunction "2_2") (pintype "passive"))
      (node (ref "U34") (pin "5") (pinfunction "S2A_5") (pintype "passive"))
    )
    (net (code "59") (name "Net-(U34-S3A)") (class "Default")
      (node (ref "R108") (pin "2") (pinfunction "2_2") (pintype "passive"))
      (node (ref "U34") (pin "6") (pinfunction "S3A_6") (pintype "passive"))
    )
    (net (code "60") (name "Net-(U34-S4A)") (class "Default")
      (node (ref "R109") (pin "2") (pinfunction "2_2") (pintype "passive"))
      (node (ref "U34") (pin "7") (pinfunction "S4A_7") (pintype "passive"))
    )
  )
)
